# CON_RS232DTE_DB9M.net
KiCad netlist of a schematic drawn in Altium Designer
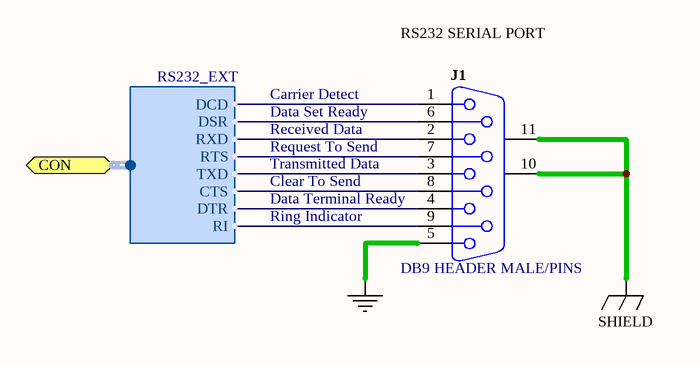
[diagram p0: CON_RS232DTE_DB9M.SchDoc]

(export (version "E")
  (design (tool "Eeschema 10.0.6"))
  (components
    (comp (ref "J1")
      (value "DB9 HEADER MALE/PINS")
      (footprint "DSUB1.9_MALE")
      (description "Connector DB9 Right-Angle Male/Pins forked-board-lock")
      (libsource (lib "AltiumDesignLibrary") (part "CON-DB-9-M-RA"))
    )
  )
  (nets
    (net (code "2") (name "/CTS") (class "Default")
      (node (ref "J1") (pin "8") (pinfunction "8_8") (pintype "passive"))
    )
    (net (code "3") (name "/DCD") (class "Default")
      (node (ref "J1") (pin "1") (pinfunction "1_1") (pintype "passive"))
    )
    (net (code "4") (name "/DSR") (class "Default")
      (node (ref "J1") (pin "6") (pinfunction "6_6") (pintype "passive"))
    )
    (net (code "5") (name "/DTR") (class "Default")
      (node (ref "J1") (pin "4") (pinfunction "4_4") (pintype "passive"))
    )
    (net (code "6") (name "/RI") (class "Default")
      (node (ref "J1") (pin "9") (pinfunction "9_9") (pintype "passive"))
    )
    (net (code "7") (name "/RTS") (class "Default")
      (node (ref "J1") (pin "7") (pinfunction "7_7") (pintype "passive"))
    )
    (net (code "8") (name "/RXD") (class "Default")
      (node (ref "J1") (pin "2") (pinfunction "2_2") (pintype "passive"))
    )
    (net (code "9") (name "/TXD") (class "Default")
      (node (ref "J1") (pin "3") (pinfunction "3_3") (pintype "passive"))
    )
    (net (code "11") (name "GND") (class "Default")
      (node (ref "J1") (pin "5") (pinfunction "5_5") (pintype "passive"))
    )
    (net (code "12") (name "SHIELD") (class "Default")
      (node (ref "J1") (pin "10") (pinfunction "MH1_10") (pintype "passive"))
      (node (ref "J1") (pin "11") (pinfunction "MH2_11") (pintype "passive"))
    )
  )
)
